# ATtiny85_Board.net
KiCad netlist of a schematic drawn in EAGLE
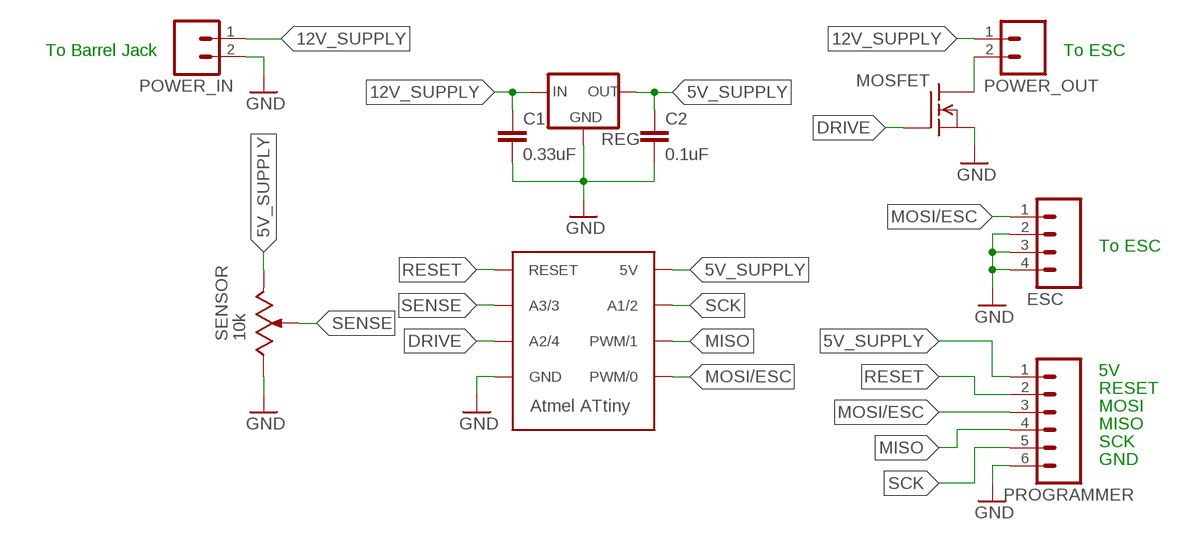
[diagram p0: schematic, sheet 1]

(export (version "E")
  (design (tool "Eeschema 10.0.6"))
  (components
    (comp (ref "C1")
      (value "0.33uF")
      (footprint "eagle-import:0805")
      (libsource (lib "eagle-import") (part "CAP0805"))
    )
    (comp (ref "C2")
      (value "0.1uF")
      (footprint "eagle-import:0805")
      (libsource (lib "eagle-import") (part "CAP0805"))
    )
    (comp (ref "ESC")
      (value "M04")
      (footprint "eagle-import:1X04")
      (libsource (lib "eagle-import") (part "M04"))
    )
    (comp (ref "MOSFET")
      (value "SI2312")
      (footprint "eagle-import:SOT-23")
      (libsource (lib "eagle-import") (part "SI2312"))
    )
    (comp (ref "POWER_IN")
      (value "M02")
      (footprint "eagle-import:1X02")
      (libsource (lib "eagle-import") (part "M02"))
    )
    (comp (ref "POWER_OUT")
      (value "M02")
      (footprint "eagle-import:1X02")
      (libsource (lib "eagle-import") (part "M02"))
    )
    (comp (ref "PROGRAMMER")
      (value "M06")
      (footprint "eagle-import:1X06")
      (libsource (lib "eagle-import") (part "M06"))
    )
    (comp (ref "REG")
      (value "L78L")
      (footprint "eagle-import:SOT-89")
      (libsource (lib "eagle-import") (part "L78L"))
    )
    (comp (ref "SENSOR")
      (value "10k")
      (footprint "eagle-import:SV03A")
      (libsource (lib "eagle-import") (part "SV03"))
    )
    (comp (ref "U$1")
      (value "ATTINY")
      (footprint "eagle-import:8S2")
      (libsource (lib "eagle-import") (part "ATTINY"))
    )
  )
  (nets
    (net (code "1") (name "5V_SUPPLY") (class "Default")
      (node (ref "C2") (pin "1") (pinfunction "1_1") (pintype "passive"))
      (node (ref "PROGRAMMER") (pin "1") (pinfunction "1_1") (pintype "passive"))
      (node (ref "REG") (pin "1") (pinfunction "OUT_1") (pintype "output"))
      (node (ref "SENSOR") (pin "1") (pinfunction "E_1") (pintype "passive"))
      (node (ref "U$1") (pin "8") (pinfunction "5V_8") (pintype "bidirectional"))
    )
    (net (code "2") (name "12V_SUPPLY") (class "Default")
      (node (ref "C1") (pin "1") (pinfunction "1_1") (pintype "passive"))
      (node (ref "POWER_IN") (pin "1") (pinfunction "1_1") (pintype "passive"))
      (node (ref "POWER_OUT") (pin "1") (pinfunction "1_1") (pintype "passive"))
      (node (ref "REG") (pin "3") (pinfunction "IN_3") (pintype "input"))
    )
    (net (code "3") (name "DRIVE") (class "Default")
      (node (ref "MOSFET") (pin "1") (pinfunction "G_1") (pintype "passive"))
      (node (ref "U$1") (pin "3") (pinfunction "A2/4_3") (pintype "bidirectional"))
    )
    (net (code "4") (name "GND") (class "Default")
      (node (ref "C1") (pin "2") (pinfunction "2_2") (pintype "passive"))
      (node (ref "C2") (pin "2") (pinfunction "2_2") (pintype "passive"))
      (node (ref "ESC") (pin "2") (pinfunction "2_2") (pintype "passive"))
      (node (ref "ESC") (pin "3") (pinfunction "3_3") (pintype "passive"))
      (node (ref "ESC") (pin "4") (pinfunction "4_4") (pintype "passive"))
      (node (ref "MOSFET") (pin "2") (pinfunction "S_2") (pintype "passive"))
      (node (ref "POWER_IN") (pin "2") (pinfunction "2_2") (pintype "passive"))
      (node (ref "PROGRAMMER") (pin "6") (pinfunction "6_6") (pintype "passive"))
      (node (ref "REG") (pin "2") (pinfunction "GND_2") (pintype "input"))
      (node (ref "REG") (pin "2.1") (pinfunction "GND_2.1") (pintype "input"))
      (node (ref "REG") (pin "2.2") (pinfunction "GND_2.2") (pintype "input"))
      (node (ref "SENSOR") (pin "3") (pinfunction "A_3") (pintype "passive"))
      (node (ref "U$1") (pin "4") (pinfunction "GND_4") (pintype "bidirectional"))
    )
    (net (code "5") (name "MISO") (class "Default")
      (node (ref "PROGRAMMER") (pin "4") (pinfunction "4_4") (pintype "passive"))
      (node (ref "U$1") (pin "6") (pinfunction "PWM/1_6") (pintype "bidirectional"))
    )
    (net (code "6") (name "MOSI{slash}ESC") (class "Default")
      (node (ref "ESC") (pin "1") (pinfunction "1_1") (pintype "passive"))
      (node (ref "PROGRAMMER") (pin "3") (pinfunction "3_3") (pintype "passive"))
      (node (ref "U$1") (pin "5") (pinfunction "PWM/0_5") (pintype "bidirectional"))
    )
    (net (code "7") (name "Net-(MOSFET-D)") (class "Default")
      (node (ref "MOSFET") (pin "3") (pinfunction "D_3") (pintype "passive"))
      (node (ref "POWER_OUT") (pin "2") (pinfunction "2_2") (pintype "passive"))
    )
    (net (code "8") (name "RESET") (class "Default")
      (node (ref "PROGRAMMER") (pin "2") (pinfunction "2_2") (pintype "passive"))
      (node (ref "U$1") (pin "1") (pinfunction "RESET_1") (pintype "bidirectional"))
    )
    (net (code "9") (name "SCK") (class "Default")
      (node (ref "PROGRAMMER") (pin "5") (pinfunction "5_5") (pintype "passive"))
      (node (ref "U$1") (pin "7") (pinfunction "A1/2_7") (pintype "bidirectional"))
    )
    (net (code "10") (name "SENSE") (class "Default")
      (node (ref "SENSOR") (pin "2") (pinfunction "S_2") (pintype "passive"))
      (node (ref "SENSOR") (pin "2.1") (pinfunction "S_2.1") (pintype "passive"))
      (node (ref "U$1") (pin "2") (pinfunction "A3/3_2") (pintype "bidirectional"))
    )
  )
)
